# Basic-Logic-Gates-Sheet.net
KiCad netlist of a schematic drawn in Altium Designer
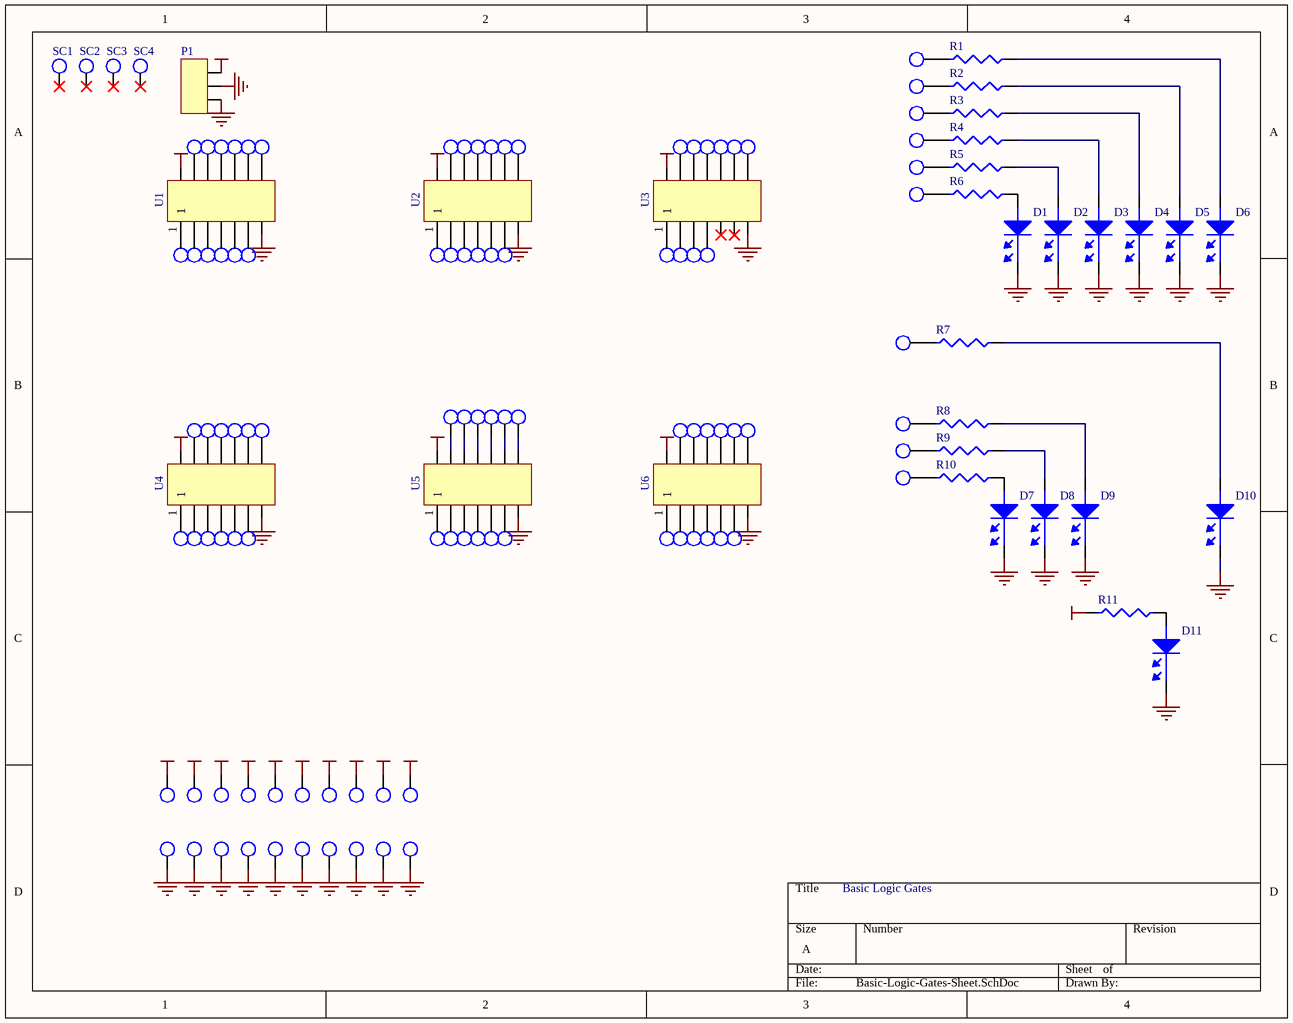
[diagram p0: Basic-Logic-Gates-Sheet.SchDoc]

(export (version "E")
  (design (tool "Eeschema 10.0.6"))
  (components
    (comp (ref "D1")
      (value "5mm LED")
      (footprint "LED")
      (libsource (lib "Basic-Logic-Gates-Schlib") (part "LED"))
    )
    (comp (ref "D2")
      (value "5mm LED")
      (footprint "LED")
      (libsource (lib "Basic-Logic-Gates-Schlib") (part "LED"))
    )
    (comp (ref "D3")
      (value "5mm LED")
      (footprint "LED")
      (libsource (lib "Basic-Logic-Gates-Schlib") (part "LED"))
    )
    (comp (ref "D4")
      (value "5mm LED")
      (footprint "LED")
      (libsource (lib "Basic-Logic-Gates-Schlib") (part "LED"))
    )
    (comp (ref "D5")
      (value "5mm LED")
      (footprint "LED")
      (libsource (lib "Basic-Logic-Gates-Schlib") (part "LED"))
    )
    (comp (ref "D6")
      (value "5mm LED")
      (footprint "LED")
      (libsource (lib "Basic-Logic-Gates-Schlib") (part "LED"))
    )
    (comp (ref "D7")
      (value "5mm LED")
      (footprint "LED")
      (libsource (lib "Basic-Logic-Gates-Schlib") (part "LED"))
    )
    (comp (ref "D8")
      (value "5mm LED")
      (footprint "LED")
      (libsource (lib "Basic-Logic-Gates-Schlib") (part "LED"))
    )
    (comp (ref "D9")
      (value "5mm LED")
      (footprint "LED")
      (libsource (lib "Basic-Logic-Gates-Schlib") (part "LED"))
    )
    (comp (ref "D10")
      (value "5mm LED")
      (footprint "LED")
      (libsource (lib "Basic-Logic-Gates-Schlib") (part "LED"))
    )
    (comp (ref "D11")
      (value "5mm LED")
      (footprint "LED")
      (libsource (lib "Basic-Logic-Gates-Schlib") (part "LED"))
    )
    (comp (ref "J1")
      (value "Jack")
      (footprint "Connector")
      (description "Jack Connector (Jumper)")
      (libsource (lib "Basic-Logic-Gates-Schlib") (part "Connector"))
    )
    (comp (ref "J2")
      (value "Jack")
      (footprint "Connector")
      (description "Jack Connector (Jumper)")
      (libsource (lib "Basic-Logic-Gates-Schlib") (part "Connector"))
    )
    (comp (ref "J3")
      (value "Jack")
      (footprint "Connector")
      (description "Jack Connector (Jumper)")
      (libsource (lib "Basic-Logic-Gates-Schlib") (part "Connector"))
    )
    (comp (ref "J4")
      (value "Jack")
      (footprint "Connector")
      (description "Jack Connector (Jumper)")
      (libsource (lib "Basic-Logic-Gates-Schlib") (part "Connector"))
    )
    (comp (ref "J5")
      (value "Jack")
      (footprint "Connector")
      (description "Jack Connector (Jumper)")
      (libsource (lib "Basic-Logic-Gates-Schlib") (part "Connector"))
    )
    (comp (ref "J6")
      (value "Jack")
      (footprint "Connector")
      (description "Jack Connector (Jumper)")
      (libsource (lib "Basic-Logic-Gates-Schlib") (part "Connector"))
    )
    (comp (ref "J7")
      (value "Jack")
      (footprint "Connector")
      (description "Jack Connector (Jumper)")
      (libsource (lib "Basic-Logic-Gates-Schlib") (part "Connector"))
    )
    (comp (ref "J8")
      (value "Jack")
      (footprint "Connector")
      (description "Jack Connector (Jumper)")
      (libsource (lib "Basic-Logic-Gates-Schlib") (part "Connector"))
    )
    (comp (ref "J9")
      (value "Jack")
      (footprint "Connector")
      (description "Jack Connector (Jumper)")
      (libsource (lib "Basic-Logic-Gates-Schlib") (part "Connector"))
    )
    (comp (ref "J10")
      (value "Jack")
      (footprint "Connector")
      (description "Jack Connector (Jumper)")
      (libsource (lib "Basic-Logic-Gates-Schlib") (part "Connector"))
    )
    (comp (ref "J11")
      (value "Jack")
      (footprint "Connector")
      (description "Jack Connector (Jumper)")
      (libsource (lib "Basic-Logic-Gates-Schlib") (part "Connector"))
    )
    (comp (ref "J12")
      (value "Jack")
      (footprint "Connector")
      (description "Jack Connector (Jumper)")
      (libsource (lib "Basic-Logic-Gates-Schlib") (part "Connector"))
    )
    (comp (ref "J13")
      (value "Jack")
      (footprint "Connector")
      (description "Jack Connector (Jumper)")
      (libsource (lib "Basic-Logic-Gates-Schlib") (part "Connector"))
    )
    (comp (ref "J14")
      (value "Jack")
      (footprint "Connector")
      (description "Jack Connector (Jumper)")
      (libsource (lib "Basic-Logic-Gates-Schlib") (part "Connector"))
    )
    (comp (ref "J15")
      (value "Jack")
      (footprint "Connector")
      (description "Jack Connector (Jumper)")
      (libsource (lib "Basic-Logic-Gates-Schlib") (part "Connector"))
    )
    (comp (ref "J16")
      (value "Jack")
      (footprint "Connector")
      (description "Jack Connector (Jumper)")
      (libsource (lib "Basic-Logic-Gates-Schlib") (part "Connector"))
    )
    (comp (ref "J17")
      (value "Jack")
      (footprint "Connector")
      (description "Jack Connector (Jumper)")
      (libsource (lib "Basic-Logic-Gates-Schlib") (part "Connector"))
    )
    (comp (ref "J18")
      (value "Jack")
      (footprint "Connector")
      (description "Jack Connector (Jumper)")
      (libsource (lib "Basic-Logic-Gates-Schlib") (part "Connector"))
    )
    (comp (ref "J19")
      (value "Jack")
      (footprint "Connector")
      (description "Jack Connector (Jumper)")
      (libsource (lib "Basic-Logic-Gates-Schlib") (part "Connector"))
    )
    (comp (ref "J20")
      (value "Jack")
      (footprint "Connector")
      (description "Jack Connector (Jumper)")
      (libsource (lib "Basic-Logic-Gates-Schlib") (part "Connector"))
    )
    (comp (ref "J21")
      (value "Jack")
      (footprint "Connector")
      (description "Jack Connector (Jumper)")
      (libsource (lib "Basic-Logic-Gates-Schlib") (part "Connector"))
    )
    (comp (ref "J22")
      (value "Jack")
      (footprint "Connector")
      (description "Jack Connector (Jumper)")
      (libsource (lib "Basic-Logic-Gates-Schlib") (part "Connector"))
    )
    (comp (ref "J23")
      (value "Jack")
      (footprint "Connector")
      (description "Jack Connector (Jumper)")
      (libsource (lib "Basic-Logic-Gates-Schlib") (part "Connector"))
    )
    (comp (ref "J24")
      (value "Jack")
      (footprint "Connector")
      (description "Jack Connector (Jumper)")
      (libsource (lib "Basic-Logic-Gates-Schlib") (part "Connector"))
    )
    (comp (ref "J25")
      (value "Jack")
      (footprint "Connector")
      (description "Jack Connector (Jumper)")
      (libsource (lib "Basic-Logic-Gates-Schlib") (part "Connector"))
    )
    (comp (ref "J26")
      (value "Jack")
      (footprint "Connector")
      (description "Jack Connector (Jumper)")
      (libsource (lib "Basic-Logic-Gates-Schlib") (part "Connector"))
    )
    (comp (ref "J27")
      (value "Jack")
      (footprint "Connector")
      (description "Jack Connector (Jumper)")
      (libsource (lib "Basic-Logic-Gates-Schlib") (part "Connector"))
    )
    (comp (ref "J28")
      (value "Jack")
      (footprint "Connector")
      (description "Jack Connector (Jumper)")
      (libsource (lib "Basic-Logic-Gates-Schlib") (part "Connector"))
    )
    (comp (ref "J29")
      (value "Jack")
      (footprint "Connector")
      (description "Jack Connector (Jumper)")
      (libsource (lib "Basic-Logic-Gates-Schlib") (part "Connector"))
    )
    (comp (ref "J30")
      (value "Jack")
      (footprint "Connector")
      (description "Jack Connector (Jumper)")
      (libsource (lib "Basic-Logic-Gates-Schlib") (part "Connector"))
    )
    (comp (ref "J31")
      (value "Jack")
      (footprint "Connector")
      (description "Jack Connector (Jumper)")
      (libsource (lib "Basic-Logic-Gates-Schlib") (part "Connector"))
    )
    (comp (ref "J32")
      (value "Jack")
      (footprint "Connector")
      (description "Jack Connector (Jumper)")
      (libsource (lib "Basic-Logic-Gates-Schlib") (part "Connector"))
    )
    (comp (ref "J33")
      (value "Jack")
      (footprint "Connector")
      (description "Jack Connector (Jumper)")
      (libsource (lib "Basic-Logic-Gates-Schlib") (part "Connector"))
    )
    (comp (ref "J34")
      (value "Jack")
      (footprint "Connector")
      (description "Jack Connector (Jumper)")
      (libsource (lib "Basic-Logic-Gates-Schlib") (part "Connector"))
    )
    (comp (ref "J35")
      (value "Jack")
      (footprint "Connector")
      (description "Jack Connector (Jumper)")
      (libsource (lib "Basic-Logic-Gates-Schlib") (part "Connector"))
    )
    (comp (ref "J36")
      (value "Jack")
      (footprint "Connector")
      (description "Jack Connector (Jumper)")
      (libsource (lib "Basic-Logic-Gates-Schlib") (part "Connector"))
    )
    (comp (ref "J37")
      (value "Jack")
      (footprint "Connector")
      (description "Jack Connector (Jumper)")
      (libsource (lib "Basic-Logic-Gates-Schlib") (part "Connector"))
    )
    (comp (ref "J38")
      (value "Jack")
      (footprint "Connector")
      (description "Jack Connector (Jumper)")
      (libsource (lib "Basic-Logic-Gates-Schlib") (part "Connector"))
    )
    (comp (ref "J39")
      (value "Jack")
      (footprint "Connector")
      (description "Jack Connector (Jumper)")
      (libsource (lib "Basic-Logic-Gates-Schlib") (part "Connector"))
    )
    (comp (ref "J40")
      (value "Jack")
      (footprint "Connector")
      (description "Jack Connector (Jumper)")
      (libsource (lib "Basic-Logic-Gates-Schlib") (part "Connector"))
    )
    (comp (ref "J41")
      (value "Jack")
      (footprint "Connector")
      (description "Jack Connector (Jumper)")
      (libsource (lib "Basic-Logic-Gates-Schlib") (part "Connector"))
    )
    (comp (ref "J42")
      (value "Jack")
      (footprint "Connector")
      (description "Jack Connector (Jumper)")
      (libsource (lib "Basic-Logic-Gates-Schlib") (part "Connector"))
    )
    (comp (ref "J43")
      (value "Jack")
      (footprint "Connector")
      (description "Jack Connector (Jumper)")
      (libsource (lib "Basic-Logic-Gates-Schlib") (part "Connector"))
    )
    (comp (ref "J44")
      (value "Jack")
      (footprint "Connector")
      (description "Jack Connector (Jumper)")
      (libsource (lib "Basic-Logic-Gates-Schlib") (part "Connector"))
    )
    (comp (ref "J45")
      (value "Jack")
      (footprint "Connector")
      (description "Jack Connector (Jumper)")
      (libsource (lib "Basic-Logic-Gates-Schlib") (part "Connector"))
    )
    (comp (ref "J46")
      (value "Jack")
      (footprint "Connector")
      (description "Jack Connector (Jumper)")
      (libsource (lib "Basic-Logic-Gates-Schlib") (part "Connector"))
    )
    (comp (ref "J47")
      (value "Jack")
      (footprint "Connector")
      (description "Jack Connector (Jumper)")
      (libsource (lib "Basic-Logic-Gates-Schlib") (part "Connector"))
    )
    (comp (ref "J48")
      (value "Jack")
      (footprint "Connector")
      (description "Jack Connector (Jumper)")
      (libsource (lib "Basic-Logic-Gates-Schlib") (part "Connector"))
    )
    (comp (ref "J49")
      (value "Jack")
      (footprint "Connector")
      (description "Jack Connector (Jumper)")
      (libsource (lib "Basic-Logic-Gates-Schlib") (part "Connector"))
    )
    (comp (ref "J50")
      (value "Jack")
      (footprint "Connector")
      (description "Jack Connector (Jumper)")
      (libsource (lib "Basic-Logic-Gates-Schlib") (part "Connector"))
    )
    (comp (ref "J51")
      (value "Jack")
      (footprint "Connector")
      (description "Jack Connector (Jumper)")
      (libsource (lib "Basic-Logic-Gates-Schlib") (part "Connector"))
    )
    (comp (ref "J52")
      (value "Jack")
      (footprint "Connector")
      (description "Jack Connector (Jumper)")
      (libsource (lib "Basic-Logic-Gates-Schlib") (part "Connector"))
    )
    (comp (ref "J53")
      (value "Jack")
      (footprint "Connector")
      (description "Jack Connector (Jumper)")
      (libsource (lib "Basic-Logic-Gates-Schlib") (part "Connector"))
    )
    (comp (ref "J54")
      (value "Jack")
      (footprint "Connector")
      (description "Jack Connector (Jumper)")
      (libsource (lib "Basic-Logic-Gates-Schlib") (part "Connector"))
    )
    (comp (ref "J55")
      (value "Jack")
      (footprint "Connector")
      (description "Jack Connector (Jumper)")
      (libsource (lib "Basic-Logic-Gates-Schlib") (part "Connector"))
    )
    (comp (ref "J56")
      (value "Jack")
      (footprint "Connector")
      (description "Jack Connector (Jumper)")
      (libsource (lib "Basic-Logic-Gates-Schlib") (part "Connector"))
    )
    (comp (ref "J57")
      (value "Jack")
      (footprint "Connector")
      (description "Jack Connector (Jumper)")
      (libsource (lib "Basic-Logic-Gates-Schlib") (part "Connector"))
    )
    (comp (ref "J58")
      (value "Jack")
      (footprint "Connector")
      (description "Jack Connector (Jumper)")
      (libsource (lib "Basic-Logic-Gates-Schlib") (part "Connector"))
    )
    (comp (ref "J59")
      (value "Jack")
      (footprint "Connector")
      (description "Jack Connector (Jumper)")
      (libsource (lib "Basic-Logic-Gates-Schlib") (part "Connector"))
    )
    (comp (ref "J60")
      (value "Jack")
      (footprint "Connector")
      (description "Jack Connector (Jumper)")
      (libsource (lib "Basic-Logic-Gates-Schlib") (part "Connector"))
    )
    (comp (ref "J61")
      (value "Jack")
      (footprint "Connector")
      (description "Jack Connector (Jumper)")
      (libsource (lib "Basic-Logic-Gates-Schlib") (part "Connector"))
    )
    (comp (ref "J62")
      (value "Jack")
      (footprint "Connector")
      (description "Jack Connector (Jumper)")
      (libsource (lib "Basic-Logic-Gates-Schlib") (part "Connector"))
    )
    (comp (ref "J63")
      (value "Jack")
      (footprint "Connector")
      (description "Jack Connector (Jumper)")
      (libsource (lib "Basic-Logic-Gates-Schlib") (part "Connector"))
    )
    (comp (ref "J64")
      (value "Jack")
      (footprint "Connector")
      (description "Jack Connector (Jumper)")
      (libsource (lib "Basic-Logic-Gates-Schlib") (part "Connector"))
    )
    (comp (ref "J65")
      (value "Jack")
      (footprint "Connector")
      (description "Jack Connector (Jumper)")
      (libsource (lib "Basic-Logic-Gates-Schlib") (part "Connector"))
    )
    (comp (ref "J66")
      (value "Jack")
      (footprint "Connector")
      (description "Jack Connector (Jumper)")
      (libsource (lib "Basic-Logic-Gates-Schlib") (part "Connector"))
    )
    (comp (ref "J67")
      (value "Jack")
      (footprint "Connector")
      (description "Jack Connector (Jumper)")
      (libsource (lib "Basic-Logic-Gates-Schlib") (part "Connector"))
    )
    (comp (ref "J68")
      (value "Jack")
      (footprint "Connector")
      (description "Jack Connector (Jumper)")
      (libsource (lib "Basic-Logic-Gates-Schlib") (part "Connector"))
    )
    (comp (ref "J69")
      (value "Jack")
      (footprint "Connector")
      (description "Jack Connector (Jumper)")
      (libsource (lib "Basic-Logic-Gates-Schlib") (part "Connector"))
    )
    (comp (ref "J70")
      (value "Jack")
      (footprint "Connector")
      (description "Jack Connector (Jumper)")
      (libsource (lib "Basic-Logic-Gates-Schlib") (part "Connector"))
    )
    (comp (ref "J71")
      (value "Jack")
      (footprint "Connector")
      (description "Jack Connector (Jumper)")
      (libsource (lib "Basic-Logic-Gates-Schlib") (part "Connector"))
    )
    (comp (ref "J72")
      (value "Jack")
      (footprint "Connector")
      (description "Jack Connector (Jumper)")
      (libsource (lib "Basic-Logic-Gates-Schlib") (part "Connector"))
    )
    (comp (ref "J73")
      (value "Jack")
      (footprint "Connector")
      (description "Jack Connector (Jumper)")
      (libsource (lib "Basic-Logic-Gates-Schlib") (part "Connector"))
    )
    (comp (ref "J74")
      (value "Jack")
      (footprint "Connector")
      (description "Jack Connector (Jumper)")
      (libsource (lib "Basic-Logic-Gates-Schlib") (part "Connector"))
    )
    (comp (ref "J75")
      (value "Jack")
      (footprint "Connector")
      (description "Jack Connector (Jumper)")
      (libsource (lib "Basic-Logic-Gates-Schlib") (part "Connector"))
    )
    (comp (ref "J76")
      (value "Jack")
      (footprint "Connector")
      (description "Jack Connector (Jumper)")
      (libsource (lib "Basic-Logic-Gates-Schlib") (part "Connector"))
    )
    (comp (ref "J77")
      (value "Jack")
      (footprint "Connector")
      (description "Jack Connector (Jumper)")
      (libsource (lib "Basic-Logic-Gates-Schlib") (part "Connector"))
    )
    (comp (ref "J78")
      (value "Jack")
      (footprint "Connector")
      (description "Jack Connector (Jumper)")
      (libsource (lib "Basic-Logic-Gates-Schlib") (part "Connector"))
    )
    (comp (ref "J79")
      (value "Jack")
      (footprint "Connector")
      (description "Jack Connector (Jumper)")
      (libsource (lib "Basic-Logic-Gates-Schlib") (part "Connector"))
    )
    (comp (ref "J80")
      (value "Jack")
      (footprint "Connector")
      (description "Jack Connector (Jumper)")
      (libsource (lib "Basic-Logic-Gates-Schlib") (part "Connector"))
    )
    (comp (ref "J81")
      (value "Jack")
      (footprint "Connector")
      (description "Jack Connector (Jumper)")
      (libsource (lib "Basic-Logic-Gates-Schlib") (part "Connector"))
    )
    (comp (ref "J82")
      (value "Jack")
      (footprint "Connector")
      (description "Jack Connector (Jumper)")
      (libsource (lib "Basic-Logic-Gates-Schlib") (part "Connector"))
    )
    (comp (ref "J83")
      (value "Jack")
      (footprint "Connector")
      (description "Jack Connector (Jumper)")
      (libsource (lib "Basic-Logic-Gates-Schlib") (part "Connector"))
    )
    (comp (ref "J84")
      (value "Jack")
      (footprint "Connector")
      (description "Jack Connector (Jumper)")
      (libsource (lib "Basic-Logic-Gates-Schlib") (part "Connector"))
    )
    (comp (ref "J85")
      (value "Jack")
      (footprint "Connector")
      (description "Jack Connector (Jumper)")
      (libsource (lib "Basic-Logic-Gates-Schlib") (part "Connector"))
    )
    (comp (ref "J86")
      (value "Jack")
      (footprint "Connector")
      (description "Jack Connector (Jumper)")
      (libsource (lib "Basic-Logic-Gates-Schlib") (part "Connector"))
    )
    (comp (ref "J87")
      (value "Jack")
      (footprint "Connector")
      (description "Jack Connector (Jumper)")
      (libsource (lib "Basic-Logic-Gates-Schlib") (part "Connector"))
    )
    (comp (ref "J88")
      (value "Jack")
      (footprint "Connector")
      (description "Jack Connector (Jumper)")
      (libsource (lib "Basic-Logic-Gates-Schlib") (part "Connector"))
    )
    (comp (ref "J89")
      (value "Jack")
      (footprint "Connector")
      (description "Jack Connector (Jumper)")
      (libsource (lib "Basic-Logic-Gates-Schlib") (part "Connector"))
    )
    (comp (ref "J90")
      (value "Jack")
      (footprint "Connector")
      (description "Jack Connector (Jumper)")
      (libsource (lib "Basic-Logic-Gates-Schlib") (part "Connector"))
    )
    (comp (ref "J91")
      (value "Jack")
      (footprint "Connector")
      (description "Jack Connector (Jumper)")
      (libsource (lib "Basic-Logic-Gates-Schlib") (part "Connector"))
    )
    (comp (ref "J92")
      (value "Jack")
      (footprint "Connector")
      (description "Jack Connector (Jumper)")
      (libsource (lib "Basic-Logic-Gates-Schlib") (part "Connector"))
    )
    (comp (ref "J93")
      (value "Jack")
      (footprint "Connector")
      (description "Jack Connector (Jumper)")
      (libsource (lib "Basic-Logic-Gates-Schlib") (part "Connector"))
    )
    (comp (ref "J94")
      (value "Jack")
      (footprint "Connector")
      (description "Jack Connector (Jumper)")
      (libsource (lib "Basic-Logic-Gates-Schlib") (part "Connector"))
    )
    (comp (ref "J95")
      (value "Jack")
      (footprint "Connector")
      (description "Jack Connector (Jumper)")
      (libsource (lib "Basic-Logic-Gates-Schlib") (part "Connector"))
    )
    (comp (ref "J96")
      (value "Jack")
      (footprint "Connector")
      (description "Jack Connector (Jumper)")
      (libsource (lib "Basic-Logic-Gates-Schlib") (part "Connector"))
    )
    (comp (ref "J97")
      (value "Jack")
      (footprint "Connector")
      (description "Jack Connector (Jumper)")
      (libsource (lib "Basic-Logic-Gates-Schlib") (part "Connector"))
    )
    (comp (ref "J98")
      (value "Jack")
      (footprint "Connector")
      (description "Jack Connector (Jumper)")
      (libsource (lib "Basic-Logic-Gates-Schlib") (part "Connector"))
    )
    (comp (ref "J99")
      (value "Jack")
      (footprint "Connector")
      (description "Jack Connector (Jumper)")
      (libsource (lib "Basic-Logic-Gates-Schlib") (part "Connector"))
    )
    (comp (ref "J100")
      (value "Jack")
      (footprint "Connector")
      (description "Jack Connector (Jumper)")
      (libsource (lib "Basic-Logic-Gates-Schlib") (part "Connector"))
    )
    (comp (ref "P1")
      (value "Power-Point")
      (footprint "Power-Point")
      (description "Power supply from encloser connection point")
      (libsource (lib "Basic-Logic-Gates-Schlib") (part "Power-Point"))
    )
    (comp (ref "R1")
      (value "Through Hole Resistor")
      (footprint "TH-Resistor")
      (libsource (lib "Basic-Logic-Gates-Schlib") (part "Resistor"))
    )
    (comp (ref "R2")
      (value "Through Hole Resistor")
      (footprint "TH-Resistor")
      (libsource (lib "Basic-Logic-Gates-Schlib") (part "Resistor"))
    )
    (comp (ref "R3")
      (value "Through Hole Resistor")
      (footprint "TH-Resistor")
      (libsource (lib "Basic-Logic-Gates-Schlib") (part "Resistor"))
    )
    (comp (ref "R4")
      (value "Through Hole Resistor")
      (footprint "TH-Resistor")
      (libsource (lib "Basic-Logic-Gates-Schlib") (part "Resistor"))
    )
    (comp (ref "R5")
      (value "Through Hole Resistor")
      (footprint "TH-Resistor")
      (libsource (lib "Basic-Logic-Gates-Schlib") (part "Resistor"))
    )
    (comp (ref "R6")
      (value "Through Hole Resistor")
      (footprint "TH-Resistor")
      (libsource (lib "Basic-Logic-Gates-Schlib") (part "Resistor"))
    )
    (comp (ref "R7")
      (value "Through Hole Resistor")
      (footprint "TH-Resistor")
      (libsource (lib "Basic-Logic-Gates-Schlib") (part "Resistor"))
    )
    (comp (ref "R8")
      (value "Through Hole Resistor")
      (footprint "TH-Resistor")
      (libsource (lib "Basic-Logic-Gates-Schlib") (part "Resistor"))
    )
    (comp (ref "R9")
      (value "Through Hole Resistor")
      (footprint "TH-Resistor")
      (libsource (lib "Basic-Logic-Gates-Schlib") (part "Resistor"))
    )
    (comp (ref "R10")
      (value "Through Hole Resistor")
      (footprint "TH-Resistor")
      (libsource (lib "Basic-Logic-Gates-Schlib") (part "Resistor"))
    )
    (comp (ref "R11")
      (value "Through Hole Resistor")
      (footprint "TH-Resistor")
      (libsource (lib "Basic-Logic-Gates-Schlib") (part "Resistor"))
    )
    (comp (ref "SC1")
      (value "Screw-Hole-Point")
      (footprint "Screw-Hole-Point")
      (libsource (lib "Basic-Logic-Gates-Schlib") (part "Screw-Hole-Point"))
    )
    (comp (ref "SC2")
      (value "Screw-Hole-Point")
      (footprint "Screw-Hole-Point")
      (libsource (lib "Basic-Logic-Gates-Schlib") (part "Screw-Hole-Point"))
    )
    (comp (ref "SC3")
      (value "Screw-Hole-Point")
      (footprint "Screw-Hole-Point")
      (libsource (lib "Basic-Logic-Gates-Schlib") (part "Screw-Hole-Point"))
    )
    (comp (ref "SC4")
      (value "Screw-Hole-Point")
      (footprint "Screw-Hole-Point")
      (libsource (lib "Basic-Logic-Gates-Schlib") (part "Screw-Hole-Point"))
    )
    (comp (ref "U1")
      (value "7400 series IC base")
      (footprint "DIP14")
      (libsource (lib "Basic-Logic-Gates-Schlib") (part "DIP14"))
    )
    (comp (ref "U2")
      (value "7400 series IC base")
      (footprint "DIP14")
      (libsource (lib "Basic-Logic-Gates-Schlib") (part "DIP14"))
    )
    (comp (ref "U3")
      (value "7400 series IC base")
      (footprint "DIP14")
      (libsource (lib "Basic-Logic-Gates-Schlib") (part "DIP14"))
    )
    (comp (ref "U4")
      (value "7400 series IC base")
      (footprint "DIP14")
      (libsource (lib "Basic-Logic-Gates-Schlib") (part "DIP14"))
    )
    (comp (ref "U5")
      (value "7400 series IC base")
      (footprint "DIP14")
      (libsource (lib "Basic-Logic-Gates-Schlib") (part "DIP14"))
    )
    (comp (ref "U6")
      (value "7400 series IC base")
      (footprint "DIP14")
      (libsource (lib "Basic-Logic-Gates-Schlib") (part "DIP14"))
    )
  )
  (nets
    (net (code "1") (name "+5") (class "Default")
      (node (ref "J81") (pin "1") (pinfunction "1_1") (pintype "passive"))
      (node (ref "J82") (pin "1") (pinfunction "1_1") (pintype "passive"))
      (node (ref "J83") (pin "1") (pinfunction "1_1") (pintype "passive"))
      (node (ref "J84") (pin "1") (pinfunction "1_1") (pintype "passive"))
      (node (ref "J85") (pin "1") (pinfunction "1_1") (pintype "passive"))
      (node (ref "J86") (pin "1") (pinfunction "1_1") (pintype "passive"))
      (node (ref "J87") (pin "1") (pinfunction "1_1") (pintype "passive"))
      (node (ref "J88") (pin "1") (pinfunction "1_1") (pintype "passive"))
      (node (ref "J89") (pin "1") (pinfunction "1_1") (pintype "passive"))
      (node (ref "J90") (pin "1") (pinfunction "1_1") (pintype "passive"))
      (node (ref "P1") (pin "1") (pinfunction "VCC_1") (pintype "passive"))
      (node (ref "R11") (pin "1") (pinfunction "1_1") (pintype "passive"))
      (node (ref "U1") (pin "14") (pinfunction "14_14") (pintype "passive"))
      (node (ref "U2") (pin "14") (pinfunction "14_14") (pintype "passive"))
      (node (ref "U3") (pin "14") (pinfunction "14_14") (pintype "passive"))
      (node (ref "U4") (pin "14") (pinfunction "14_14") (pintype "passive"))
      (node (ref "U5") (pin "14") (pinfunction "14_14") (pintype "passive"))
      (node (ref "U6") (pin "14") (pinfunction "14_14") (pintype "passive"))
    )
    (net (code "2") (name "GND") (class "Default")
      (node (ref "D1") (pin "1") (pinfunction "1_1") (pintype "passive"))
      (node (ref "D10") (pin "1") (pinfunction "1_1") (pintype "passive"))
      (node (ref "D11") (pin "1") (pinfunction "1_1") (pintype "passive"))
      (node (ref "D2") (pin "1") (pinfunction "1_1") (pintype "passive"))
      (node (ref "D3") (pin "1") (pinfunction "1_1") (pintype "passive"))
      (node (ref "D4") (pin "1") (pinfunction "1_1") (pintype "passive"))
      (node (ref "D5") (pin "1") (pinfunction "1_1") (pintype "passive"))
      (node (ref "D6") (pin "1") (pinfunction "1_1") (pintype "passive"))
      (node (ref "D7") (pin "1") (pinfunction "1_1") (pintype "passive"))
      (node (ref "D8") (pin "1") (pinfunction "1_1") (pintype "passive"))
      (node (ref "D9") (pin "1") (pinfunction "1_1") (pintype "passive"))
      (node (ref "J100") (pin "1") (pinfunction "1_1") (pintype "passive"))
      (node (ref "J91") (pin "1") (pinfunction "1_1") (pintype "passive"))
      (node (ref "J92") (pin "1") (pinfunction "1_1") (pintype "passive"))
      (node (ref "J93") (pin "1") (pinfunction "1_1") (pintype "passive"))
      (node (ref "J94") (pin "1") (pinfunction "1_1") (pintype "passive"))
      (node (ref "J95") (pin "1") (pinfunction "1_1") (pintype "passive"))
      (node (ref "J96") (pin "1") (pinfunction "1_1") (pintype "passive"))
      (node (ref "J97") (pin "1") (pinfunction "1_1") (pintype "passive"))
      (node (ref "J98") (pin "1") (pinfunction "1_1") (pintype "passive"))
      (node (ref "J99") (pin "1") (pinfunction "1_1") (pintype "passive"))
      (node (ref "P1") (pin "2") (pinfunction "GND_2") (pintype "passive"))
      (node (ref "P1") (pin "3") (pinfunction "GND_3") (pintype "passive"))
      (node (ref "U1") (pin "7") (pinfunction "7_7") (pintype "passive"))
      (node (ref "U2") (pin "7") (pinfunction "7_7") (pintype "passive"))
      (node (ref "U3") (pin "7") (pinfunction "7_7") (pintype "passive"))
      (node (ref "U4") (pin "7") (pinfunction "7_7") (pintype "passive"))
      (node (ref "U5") (pin "7") (pinfunction "7_7") (pintype "passive"))
      (node (ref "U6") (pin "7") (pinfunction "7_7") (pintype "passive"))
    )
    (net (code "3") (name "Net-(D1-Pad2)") (class "Default")
      (node (ref "D1") (pin "2") (pinfunction "2_2") (pintype "passive"))
      (node (ref "R6") (pin "2") (pinfunction "2_2") (pintype "passive"))
    )
    (net (code "4") (name "Net-(D2-Pad2)") (class "Default")
      (node (ref "D2") (pin "2") (pinfunction "2_2") (pintype "passive"))
      (node (ref "R5") (pin "2") (pinfunction "2_2") (pintype "passive"))
    )
    (net (code "5") (name "Net-(D3-Pad2)") (class "Default")
      (node (ref "D3") (pin "2") (pinfunction "2_2") (pintype "passive"))
      (node (ref "R4") (pin "2") (pinfunction "2_2") (pintype "passive"))
    )
    (net (code "6") (name "Net-(D4-Pad2)") (class "Default")
      (node (ref "D4") (pin "2") (pinfunction "2_2") (pintype "passive"))
      (node (ref "R3") (pin "2") (pinfunction "2_2") (pintype "passive"))
    )
    (net (code "7") (name "Net-(D5-Pad2)") (class "Default")
      (node (ref "D5") (pin "2") (pinfunction "2_2") (pintype "passive"))
      (node (ref "R2") (pin "2") (pinfunction "2_2") (pintype "passive"))
    )
    (net (code "8") (name "Net-(D6-Pad2)") (class "Default")
      (node (ref "D6") (pin "2") (pinfunction "2_2") (pintype "passive"))
      (node (ref "R1") (pin "2") (pinfunction "2_2") (pintype "passive"))
    )
    (net (code "9") (name "Net-(D7-Pad2)") (class "Default")
      (node (ref "D7") (pin "2") (pinfunction "2_2") (pintype "passive"))
      (node (ref "R10") (pin "2") (pinfunction "2_2") (pintype "passive"))
    )
    (net (code "10") (name "Net-(D8-Pad2)") (class "Default")
      (node (ref "D8") (pin "2") (pinfunction "2_2") (pintype "passive"))
      (node (ref "R9") (pin "2") (pinfunction "2_2") (pintype "passive"))
    )
    (net (code "11") (name "Net-(D9-Pad2)") (class "Default")
      (node (ref "D9") (pin "2") (pinfunction "2_2") (pintype "passive"))
      (node (ref "R8") (pin "2") (pinfunction "2_2") (pintype "passive"))
    )
    (net (code "12") (name "Net-(D10-Pad2)") (class "Default")
      (node (ref "D10") (pin "2") (pinfunction "2_2") (pintype "passive"))
      (node (ref "R7") (pin "2") (pinfunction "2_2") (pintype "passive"))
    )
    (net (code "13") (name "Net-(D11-Pad2)") (class "Default")
      (node (ref "D11") (pin "2") (pinfunction "2_2") (pintype "passive"))
      (node (ref "R11") (pin "2") (pinfunction "2_2") (pintype "passive"))
    )
    (net (code "14") (name "Net-(J1-Pad1)") (class "Default")
      (node (ref "J1") (pin "1") (pinfunction "1_1") (pintype "passive"))
      (node (ref "R1") (pin "1") (pinfunction "1_1") (pintype "passive"))
    )
    (net (code "15") (name "Net-(J2-Pad1)") (class "Default")
      (node (ref "J2") (pin "1") (pinfunction "1_1") (pintype "passive"))
      (node (ref "R2") (pin "1") (pinfunction "1_1") (pintype "passive"))
    )
    (net (code "16") (name "Net-(J3-Pad1)") (class "Default")
      (node (ref "J3") (pin "1") (pinfunction "1_1") (pintype "passive"))
      (node (ref "R3") (pin "1") (pinfunction "1_1") (pintype "passive"))
    )
    (net (code "17") (name "Net-(J4-Pad1)") (class "Default")
      (node (ref "J4") (pin "1") (pinfunction "1_1") (pintype "passive"))
      (node (ref "R4") (pin "1") (pinfunction "1_1") (pintype "passive"))
    )
    (net (code "18") (name "Net-(J5-Pad1)") (class "Default")
      (node (ref "J5") (pin "1") (pinfunction "1_1") (pintype "passive"))
      (node (ref "U1") (pin "13") (pinfunction "13_13") (pintype "passive"))
    )
    (net (code "19") (name "Net-(J6-Pad1)") (class "Default")
      (node (ref "J6") (pin "1") (pinfunction "1_1") (pintype "passive"))
      (node (ref "U1") (pin "12") (pinfunction "12_12") (pintype "passive"))
    )
    (net (code "20") (name "Net-(J7-Pad1)") (class "Default")
      (node (ref "J7") (pin "1") (pinfunction "1_1") (pintype "passive"))
      (node (ref "U1") (pin "11") (pinfunction "11_11") (pintype "passive"))
    )
    (net (code "21") (name "Net-(J8-Pad1)") (class "Default")
      (node (ref "J8") (pin "1") (pinfunction "1_1") (pintype "passive"))
      (node (ref "U1") (pin "10") (pinfunction "10_10") (pintype "passive"))
    )
    (net (code "22") (name "Net-(J9-Pad1)") (class "Default")
      (node (ref "J9") (pin "1") (pinfunction "1_1") (pintype "passive"))
      (node (ref "U1") (pin "9") (pinfunction "9_9") (pintype "passive"))
    )
    (net (code "23") (name "Net-(J10-Pad1)") (class "Default")
      (node (ref "J10") (pin "1") (pinfunction "1_1") (pintype "passive"))
      (node (ref "U1") (pin "8") (pinfunction "8_8") (pintype "passive"))
    )
    (net (code "24") (name "Net-(J11-Pad1)") (class "Default")
      (node (ref "J11") (pin "1") (pinfunction "1_1") (pintype "passive"))
      (node (ref "U2") (pin "13") (pinfunction "13_13") (pintype "passive"))
    )
    (net (code "25") (name "Net-(J12-Pad1)") (class "Default")
      (node (ref "J12") (pin "1") (pinfunction "1_1") (pintype "passive"))
      (node (ref "U2") (pin "12") (pinfunction "12_12") (pintype "passive"))
    )
    (net (code "26") (name "Net-(J13-Pad1)") (class "Default")
      (node (ref "J13") (pin "1") (pinfunction "1_1") (pintype "passive"))
      (node (ref "U2") (pin "11") (pinfunction "11_11") (pintype "passive"))
    )
    (net (code "27") (name "Net-(J14-Pad1)") (class "Default")
      (node (ref "J14") (pin "1") (pinfunction "1_1") (pintype "passive"))
      (node (ref "U2") (pin "10") (pinfunction "10_10") (pintype "passive"))
    )
    (net (code "28") (name "Net-(J15-Pad1)") (class "Default")
      (node (ref "J15") (pin "1") (pinfunction "1_1") (pintype "passive"))
      (node (ref "U2") (pin "9") (pinfunction "9_9") (pintype "passive"))
    )
    (net (code "29") (name "Net-(J16-Pad1)") (class "Default")
      (node (ref "J16") (pin "1") (pinfunction "1_1") (pintype "passive"))
      (node (ref "U2") (pin "8") (pinfunction "8_8") (pintype "passive"))
    )
    (net (code "30") (name "Net-(J17-Pad1)") (class "Default")
      (node (ref "J17") (pin "1") (pinfunction "1_1") (pintype "passive"))
      (node (ref "U3") (pin "13") (pinfunction "13_13") (pintype "passive"))
    )
    (net (code "31") (name "Net-(J18-Pad1)") (class "Default")
      (node (ref "J18") (pin "1") (pinfunction "1_1") (pintype "passive"))
      (node (ref "U3") (pin "12") (pinfunction "12_12") (pintype "passive"))
    )
    (net (code "32") (name "Net-(J19-Pad1)") (class "Default")
      (node (ref "J19") (pin "1") (pinfunction "1_1") (pintype "passive"))
      (node (ref "U3") (pin "11") (pinfunction "11_11") (pintype "passive"))
    )
    (net (code "33") (name "Net-(J20-Pad1)") (class "Default")
      (node (ref "J20") (pin "1") (pinfunction "1_1") (pintype "passive"))
      (node (ref "U3") (pin "10") (pinfunction "10_10") (pintype "passive"))
    )
    (net (code "34") (name "Net-(J21-Pad1)") (class "Default")
      (node (ref "J21") (pin "1") (pinfunction "1_1") (pintype "passive"))
      (node (ref "U3") (pin "9") (pinfunction "9_9") (pintype "passive"))
    )
    (net (code "35") (name "Net-(J22-Pad1)") (class "Default")
      (node (ref "J22") (pin "1") (pinfunction "1_1") (pintype "passive"))
      (node (ref "U3") (pin "8") (pinfunction "8_8") (pintype "passive"))
    )
    (net (code "36") (name "Net-(J23-Pad1)") (class "Default")
      (node (ref "J23") (pin "1") (pinfunction "1_1") (pintype "passive"))
      (node (ref "R5") (pin "1") (pinfunction "1_1") (pintype "passive"))
    )
    (net (code "37") (name "Net-(J24-Pad1)") (class "Default")
      (node (ref "J24") (pin "1") (pinfunction "1_1") (pintype "passive"))
      (node (ref "R6") (pin "1") (pinfunction "1_1") (pintype "passive"))
    )
    (net (code "38") (name "Net-(J25-Pad1)") (class "Default")
      (node (ref "J25") (pin "1") (pinfunction "1_1") (pintype "passive"))
      (node (ref "U1") (pin "1") (pinfunction "1_1") (pintype "passive"))
    )
    (net (code "39") (name "Net-(J26-Pad1)") (class "Default")
      (node (ref "J26") (pin "1") (pinfunction "1_1") (pintype "passive"))
      (node (ref "U1") (pin "2") (pinfunction "2_2") (pintype "passive"))
    )
    (net (code "40") (name "Net-(J27-Pad1)") (class "Default")
      (node (ref "J27") (pin "1") (pinfunction "1_1") (pintype "passive"))
      (node (ref "U1") (pin "3") (pinfunction "3_3") (pintype "passive"))
    )
    (net (code "41") (name "Net-(J28-Pad1)") (class "Default")
      (node (ref "J28") (pin "1") (pinfunction "1_1") (pintype "passive"))
      (node (ref "U1") (pin "4") (pinfunction "4_4") (pintype "passive"))
    )
    (net (code "42") (name "Net-(J29-Pad1)") (class "Default")
      (node (ref "J29") (pin "1") (pinfunction "1_1") (pintype "passive"))
      (node (ref "U1") (pin "5") (pinfunction "5_5") (pintype "passive"))
    )
    (net (code "43") (name "Net-(J30-Pad1)") (class "Default")
      (node (ref "J30") (pin "1") (pinfunction "1_1") (pintype "passive"))
      (node (ref "U1") (pin "6") (pinfunction "6_6") (pintype "passive"))
    )
    (net (code "44") (name "Net-(J31-Pad1)") (class "Default")
      (node (ref "J31") (pin "1") (pinfunction "1_1") (pintype "passive"))
      (node (ref "U2") (pin "1") (pinfunction "1_1") (pintype "passive"))
    )
    (net (code "45") (name "Net-(J32-Pad1)") (class "Default")
      (node (ref "J32") (pin "1") (pinfunction "1_1") (pintype "passive"))
      (node (ref "U2") (pin "2") (pinfunction "2_2") (pintype "passive"))
    )
    (net (code "46") (name "Net-(J33-Pad1)") (class "Default")
      (node (ref "J33") (pin "1") (pinfunction "1_1") (pintype "passive"))
      (node (ref "U2") (pin "3") (pinfunction "3_3") (pintype "passive"))
    )
    (net (code "47") (name "Net-(J34-Pad1)") (class "Default")
      (node (ref "J34") (pin "1") (pinfunction "1_1") (pintype "passive"))
      (node (ref "U2") (pin "4") (pinfunction "4_4") (pintype "passive"))
    )
    (net (code "48") (name "Net-(J35-Pad1)") (class "Default")
      (node (ref "J35") (pin "1") (pinfunction "1_1") (pintype "passive"))
      (node (ref "U2") (pin "5") (pinfunction "5_5") (pintype "passive"))
    )
    (net (code "49") (name "Net-(J36-Pad1)") (class "Default")
      (node (ref "J36") (pin "1") (pinfunction "1_1") (pintype "passive"))
      (node (ref "U2") (pin "6") (pinfunction "6_6") (pintype "passive"))
    )
    (net (code "50") (name "Net-(J37-Pad1)") (class "Default")
      (node (ref "J37") (pin "1") (pinfunction "1_1") (pintype "passive"))
      (node (ref "U3") (pin "1") (pinfunction "1_1") (pintype "passive"))
    )
    (net (code "51") (name "Net-(J38-Pad1)") (class "Default")
      (node (ref "J38") (pin "1") (pinfunction "1_1") (pintype "passive"))
      (node (ref "U3") (pin "2") (pinfunction "2_2") (pintype "passive"))
    )
    (net (code "52") (name "Net-(J39-Pad1)") (class "Default")
      (node (ref "J39") (pin "1") (pinfunction "1_1") (pintype "passive"))
      (node (ref "U3") (pin "3") (pinfunction "3_3") (pintype "passive"))
    )
    (net (code "53") (name "Net-(J40-Pad1)") (class "Default")
      (node (ref "J40") (pin "1") (pinfunction "1_1") (pintype "passive"))
      (node (ref "U3") (pin "4") (pinfunction "4_4") (pintype "passive"))
    )
    (net (code "54") (name "Net-(J41-Pad1)") (class "Default")
      (node (ref "J41") (pin "1") (pinfunction "1_1") (pintype "passive"))
      (node (ref "R7") (pin "1") (pinfunction "1_1") (pintype "passive"))
    )
    (net (code "55") (name "Net-(J42-Pad1)") (class "Default")
      (node (ref "J42") (pin "1") (pinfunction "1_1") (pintype "passive"))
      (node (ref "R8") (pin "1") (pinfunction "1_1") (pintype "passive"))
    )
    (net (code "56") (name "Net-(J43-Pad1)") (class "Default")
      (node (ref "J43") (pin "1") (pinfunction "1_1") (pintype "passive"))
      (node (ref "U5") (pin "13") (pinfunction "13_13") (pintype "passive"))
    )
    (net (code "57") (name "Net-(J44-Pad1)") (class "Default")
      (node (ref "J44") (pin "1") (pinfunction "1_1") (pintype "passive"))
      (node (ref "U5") (pin "12") (pinfunction "12_12") (pintype "passive"))
    )
    (net (code "58") (name "Net-(J45-Pad1)") (class "Default")
      (node (ref "J45") (pin "1") (pinfunction "1_1") (pintype "passive"))
      (node (ref "U5") (pin "11") (pinfunction "11_11") (pintype "passive"))
    )
    (net (code "59") (name "Net-(J46-Pad1)") (class "Default")
      (node (ref "J46") (pin "1") (pinfunction "1_1") (pintype "passive"))
      (node (ref "U5") (pin "10") (pinfunction "10_10") (pintype "passive"))
    )
    (net (code "60") (name "Net-(J47-Pad1)") (class "Default")
      (node (ref "J47") (pin "1") (pinfunction "1_1") (pintype "passive"))
      (node (ref "U5") (pin "9") (pinfunction "9_9") (pintype "passive"))
    )
    (net (code "61") (name "Net-(J48-Pad1)") (class "Default")
      (node (ref "J48") (pin "1") (pinfunction "1_1") (pintype "passive"))
      (node (ref "U5") (pin "8") (pinfunction "8_8") (pintype "passive"))
    )
    (net (code "62") (name "Net-(J49-Pad1)") (class "Default")
      (node (ref "J49") (pin "1") (pinfunction "1_1") (pintype "passive"))
      (node (ref "U4") (pin "13") (pinfunction "13_13") (pintype "passive"))
    )
    (net (code "63") (name "Net-(J50-Pad1)") (class "Default")
      (node (ref "J50") (pin "1") (pinfunction "1_1") (pintype "passive"))
      (node (ref "U4") (pin "12") (pinfunction "12_12") (pintype "passive"))
    )
    (net (code "64") (name "Net-(J51-Pad1)") (class "Default")
      (node (ref "J51") (pin "1") (pinfunction "1_1") (pintype "passive"))
      (node (ref "U4") (pin "11") (pinfunction "11_11") (pintype "passive"))
    )
    (net (code "65") (name "Net-(J52-Pad1)") (class "Default")
      (node (ref "J52") (pin "1") (pinfunction "1_1") (pintype "passive"))
      (node (ref "U4") (pin "10") (pinfunction "10_10") (pintype "passive"))
    )
    (net (code "66") (name "Net-(J53-Pad1)") (class "Default")
      (node (ref "J53") (pin "1") (pinfunction "1_1") (pintype "passive"))
      (node (ref "U4") (pin "9") (pinfunction "9_9") (pintype "passive"))
    )
    (net (code "67") (name "Net-(J54-Pad1)") (class "Default")
      (node (ref "J54") (pin "1") (pinfunction "1_1") (pintype "passive"))
      (node (ref "U4") (pin "8") (pinfunction "8_8") (pintype "passive"))
    )
    (net (code "68") (name "Net-(J55-Pad1)") (class "Default")
      (node (ref "J55") (pin "1") (pinfunction "1_1") (pintype "passive"))
      (node (ref "U6") (pin "13") (pinfunction "13_13") (pintype "passive"))
    )
    (net (code "69") (name "Net-(J56-Pad1)") (class "Default")
      (node (ref "J56") (pin "1") (pinfunction "1_1") (pintype "passive"))
      (node (ref "U6") (pin "12") (pinfunction "12_12") (pintype "passive"))
    )
    (net (code "70") (name "Net-(J57-Pad1)") (class "Default")
      (node (ref "J57") (pin "1") (pinfunction "1_1") (pintype "passive"))
      (node (ref "U6") (pin "11") (pinfunction "11_11") (pintype "passive"))
    )
    (net (code "71") (name "Net-(J58-Pad1)") (class "Default")
      (node (ref "J58") (pin "1") (pinfunction "1_1") (pintype "passive"))
      (node (ref "U6") (pin "10") (pinfunction "10_10") (pintype "passive"))
    )
    (net (code "72") (name "Net-(J59-Pad1)") (class "Default")
      (node (ref "J59") (pin "1") (pinfunction "1_1") (pintype "passive"))
      (node (ref "U6") (pin "9") (pinfunction "9_9") (pintype "passive"))
    )
    (net (code "73") (name "Net-(J60-Pad1)") (class "Default")
      (node (ref "J60") (pin "1") (pinfunction "1_1") (pintype "passive"))
      (node (ref "U6") (pin "8") (pinfunction "8_8") (pintype "passive"))
    )
    (net (code "74") (name "Net-(J61-Pad1)") (class "Default")
      (node (ref "J61") (pin "1") (pinfunction "1_1") (pintype "passive"))
      (node (ref "R9") (pin "1") (pinfunction "1_1") (pintype "passive"))
    )
    (net (code "75") (name "Net-(J62-Pad1)") (class "Default")
      (node (ref "J62") (pin "1") (pinfunction "1_1") (pintype "passive"))
      (node (ref "R10") (pin "1") (pinfunction "1_1") (pintype "passive"))
    )
    (net (code "76") (name "Net-(J63-Pad1)") (class "Default")
      (node (ref "J63") (pin "1") (pinfunction "1_1") (pintype "passive"))
      (node (ref "U4") (pin "1") (pinfunction "1_1") (pintype "passive"))
    )
    (net (code "77") (name "Net-(J64-Pad1)") (class "Default")
      (node (ref "J64") (pin "1") (pinfunction "1_1") (pintype "passive"))
      (node (ref "U4") (pin "2") (pinfunction "2_2") (pintype "passive"))
    )
    (net (code "78") (name "Net-(J65-Pad1)") (class "Default")
      (node (ref "J65") (pin "1") (pinfunction "1_1") (pintype "passive"))
      (node (ref "U4") (pin "3") (pinfunction "3_3") (pintype "passive"))
    )
    (net (code "79") (name "Net-(J66-Pad1)") (class "Default")
      (node (ref "J66") (pin "1") (pinfunction "1_1") (pintype "passive"))
      (node (ref "U4") (pin "4") (pinfunction "4_4") (pintype "passive"))
    )
    (net (code "80") (name "Net-(J67-Pad1)") (class "Default")
      (node (ref "J67") (pin "1") (pinfunction "1_1") (pintype "passive"))
      (node (ref "U4") (pin "5") (pinfunction "5_5") (pintype "passive"))
    )
    (net (code "81") (name "Net-(J68-Pad1)") (class "Default")
      (node (ref "J68") (pin "1") (pinfunction "1_1") (pintype "passive"))
      (node (ref "U4") (pin "6") (pinfunction "6_6") (pintype "passive"))
    )
    (net (code "82") (name "Net-(J69-Pad1)") (class "Default")
      (node (ref "J69") (pin "1") (pinfunction "1_1") (pintype "passive"))
      (node (ref "U5") (pin "1") (pinfunction "1_1") (pintype "passive"))
    )
    (net (code "83") (name "Net-(J70-Pad1)") (class "Default")
      (node (ref "J70") (pin "1") (pinfunction "1_1") (pintype "passive"))
      (node (ref "U5") (pin "2") (pinfunction "2_2") (pintype "passive"))
    )
    (net (code "84") (name "Net-(J71-Pad1)") (class "Default")
      (node (ref "J71") (pin "1") (pinfunction "1_1") (pintype "passive"))
      (node (ref "U5") (pin "3") (pinfunction "3_3") (pintype "passive"))
    )
    (net (code "85") (name "Net-(J72-Pad1)") (class "Default")
      (node (ref "J72") (pin "1") (pinfunction "1_1") (pintype "passive"))
      (node (ref "U5") (pin "4") (pinfunction "4_4") (pintype "passive"))
    )
    (net (code "86") (name "Net-(J73-Pad1)") (class "Default")
      (node (ref "J73") (pin "1") (pinfunction "1_1") (pintype "passive"))
      (node (ref "U5") (pin "5") (pinfunction "5_5") (pintype "passive"))
    )
    (net (code "87") (name "Net-(J74-Pad1)") (class "Default")
      (node (ref "J74") (pin "1") (pinfunction "1_1") (pintype "passive"))
      (node (ref "U5") (pin "6") (pinfunction "6_6") (pintype "passive"))
    )
    (net (code "88") (name "Net-(J75-Pad1)") (class "Default")
      (node (ref "J75") (pin "1") (pinfunction "1_1") (pintype "passive"))
      (node (ref "U6") (pin "1") (pinfunction "1_1") (pintype "passive"))
    )
    (net (code "89") (name "Net-(J76-Pad1)") (class "Default")
      (node (ref "J76") (pin "1") (pinfunction "1_1") (pintype "passive"))
      (node (ref "U6") (pin "2") (pinfunction "2_2") (pintype "passive"))
    )
    (net (code "90") (name "Net-(J77-Pad1)") (class "Default")
      (node (ref "J77") (pin "1") (pinfunction "1_1") (pintype "passive"))
      (node (ref "U6") (pin "3") (pinfunction "3_3") (pintype "passive"))
    )
    (net (code "91") (name "Net-(J78-Pad1)") (class "Default")
      (node (ref "J78") (pin "1") (pinfunction "1_1") (pintype "passive"))
      (node (ref "U6") (pin "4") (pinfunction "4_4") (pintype "passive"))
    )
    (net (code "92") (name "Net-(J79-Pad1)") (class "Default")
      (node (ref "J79") (pin "1") (pinfunction "1_1") (pintype "passive"))
      (node (ref "U6") (pin "5") (pinfunction "5_5") (pintype "passive"))
    )
    (net (code "93") (name "Net-(J80-Pad1)") (class "Default")
      (node (ref "J80") (pin "1") (pinfunction "1_1") (pintype "passive"))
      (node (ref "U6") (pin "6") (pinfunction "6_6") (pintype "passive"))
    )
    (net (code "94") (name "unconnected-(SC1-Pad1)") (class "Default")
      (node (ref "SC1") (pin "1") (pinfunction "1_1") (pintype "passive+no_connect"))
    )
    (net (code "95") (name "unconnected-(SC2-Pad1)") (class "Default")
      (node (ref "SC2") (pin "1") (pinfunction "1_1") (pintype "passive+no_connect"))
    )
    (net (code "96") (name "unconnected-(SC3-Pad1)") (class "Default")
      (node (ref "SC3") (pin "1") (pinfunction "1_1") (pintype "passive+no_connect"))
    )
    (net (code "97") (name "unconnected-(SC4-Pad1)") (class "Default")
      (node (ref "SC4") (pin "1") (pinfunction "1_1") (pintype "passive+no_connect"))
    )
    (net (code "98") (name "unconnected-(U3-Pad5)") (class "Default")
      (node (ref "U3") (pin "5") (pinfunction "5_5") (pintype "passive+no_connect"))
    )
    (net (code "99") (name "unconnected-(U3-Pad6)") (class "Default")
      (node (ref "U3") (pin "6") (pinfunction "6_6") (pintype "passive+no_connect"))
    )
  )
)
